# LedController3.net
KiCad netlist of a schematic drawn in EAGLE
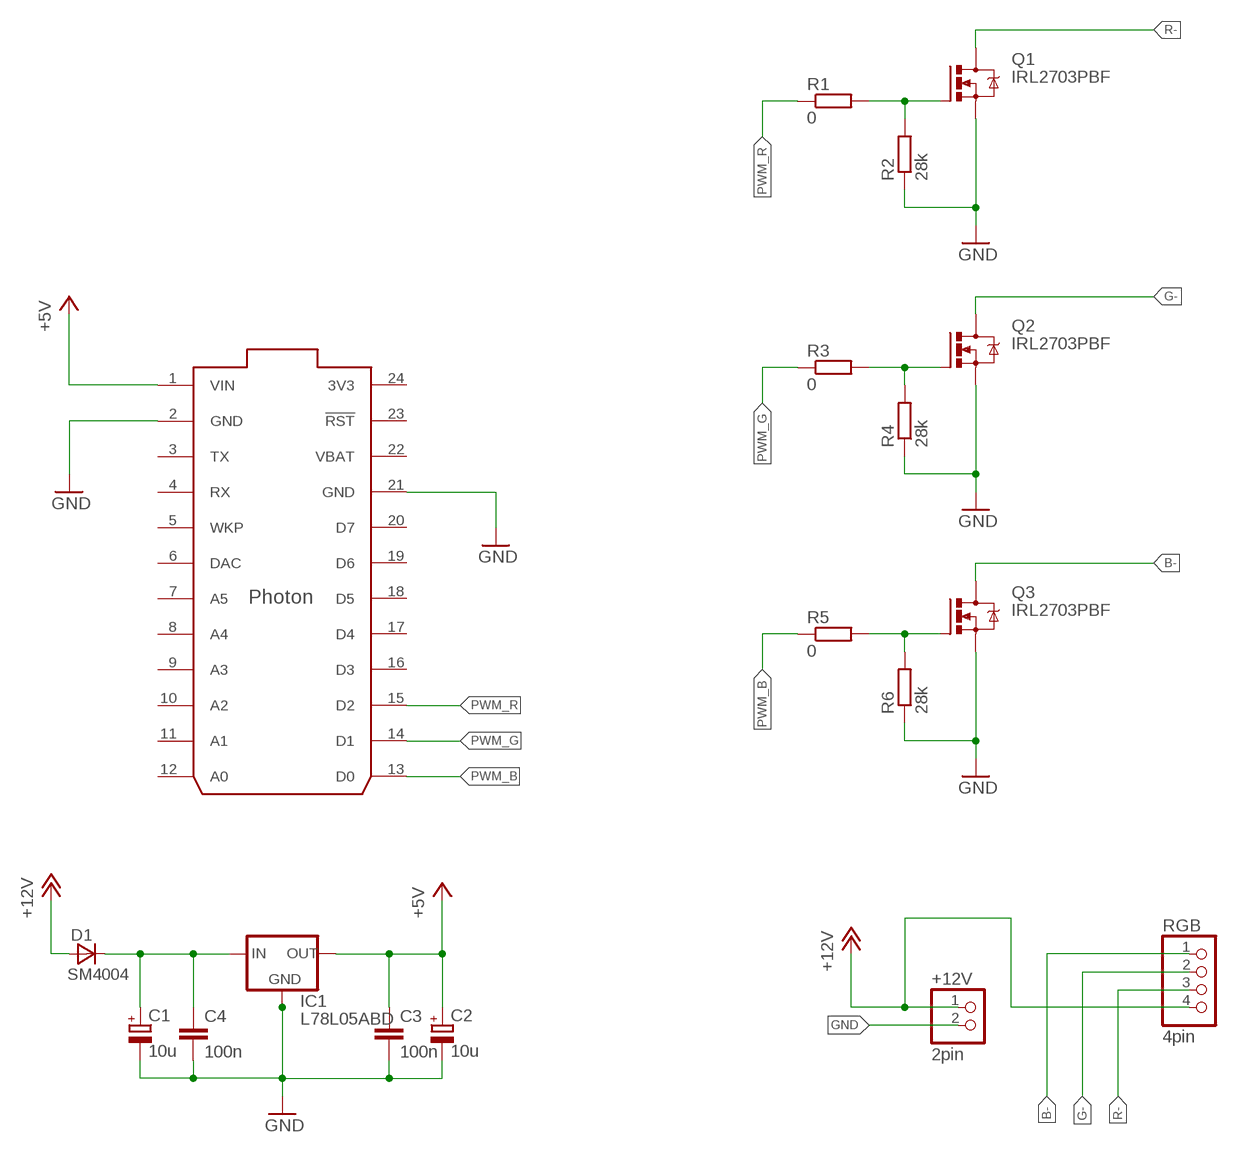
[diagram p0: schematic, sheet 1]

(export (version "E")
  (design (tool "Eeschema 10.0.6"))
  (components
    (comp (ref "+12V")
      (value "2pin")
      (footprint "eagle-import:1X02")
      (libsource (lib "eagle-import") (part "PINHD-1X2"))
    )
    (comp (ref "C1")
      (value "10u")
      (footprint "eagle-import:SMC_C")
      (libsource (lib "eagle-import") (part "CPOL-EUSMCC"))
    )
    (comp (ref "C2")
      (value "10u")
      (footprint "eagle-import:SMC_C")
      (libsource (lib "eagle-import") (part "CPOL-EUSMCC"))
    )
    (comp (ref "C3")
      (value "100n")
      (footprint "eagle-import:C0805")
      (libsource (lib "eagle-import") (part "C-EUC0805"))
    )
    (comp (ref "C4")
      (value "100n")
      (footprint "eagle-import:C0805")
      (libsource (lib "eagle-import") (part "C-EUC0805"))
    )
    (comp (ref "D1")
      (value "SM4004")
      (footprint "eagle-import:MELF-MLL41")
      (libsource (lib "eagle-import") (part "SM4004"))
    )
    (comp (ref "IC1")
      (value "L78L05ABD")
      (footprint "eagle-import:SO08")
      (libsource (lib "eagle-import") (part "L78LXXBD/CD"))
    )
    (comp (ref "Q1")
      (value "IRL2703PBF")
      (footprint "eagle-import:TO220BV")
      (libsource (lib "eagle-import") (part "IRF540"))
    )
    (comp (ref "Q2")
      (value "IRL2703PBF")
      (footprint "eagle-import:TO220BV")
      (libsource (lib "eagle-import") (part "IRF540"))
    )
    (comp (ref "Q3")
      (value "IRL2703PBF")
      (footprint "eagle-import:TO220BV")
      (libsource (lib "eagle-import") (part "IRF540"))
    )
    (comp (ref "R1")
      (value "0")
      (footprint "eagle-import:R0805")
      (libsource (lib "eagle-import") (part "R-EU_R0805"))
    )
    (comp (ref "R2")
      (value "28k")
      (footprint "eagle-import:R0805")
      (libsource (lib "eagle-import") (part "R-EU_R0805"))
    )
    (comp (ref "R3")
      (value "0")
      (footprint "eagle-import:R0805")
      (libsource (lib "eagle-import") (part "R-EU_R0805"))
    )
    (comp (ref "R4")
      (value "28k")
      (footprint "eagle-import:R0805")
      (libsource (lib "eagle-import") (part "R-EU_R0805"))
    )
    (comp (ref "R5")
      (value "0")
      (footprint "eagle-import:R0805")
      (libsource (lib "eagle-import") (part "R-EU_R0805"))
    )
    (comp (ref "R6")
      (value "28k")
      (footprint "eagle-import:R0805")
      (libsource (lib "eagle-import") (part "R-EU_R0805"))
    )
    (comp (ref "RGB")
      (value "4pin")
      (footprint "eagle-import:1X04")
      (libsource (lib "eagle-import") (part "PINHD-1X4"))
    )
    (comp (ref "U$1")
      (value "PHOTON_WITH_HEADERS")
      (footprint "eagle-import:PHOTON")
      (libsource (lib "eagle-import") (part "PHOTON_WITH_HEADERS"))
    )
  )
  (nets
    (net (code "1") (name "+5V") (class "Default")
      (node (ref "C2") (pin "+") (pinfunction "+_+") (pintype "passive"))
      (node (ref "C3") (pin "1") (pinfunction "1_1") (pintype "passive"))
      (node (ref "IC1") (pin "1") (pinfunction "OUT_1") (pintype "passive"))
      (node (ref "U$1") (pin "1") (pinfunction "VIN_1") (pintype "power_in"))
    )
    (net (code "2") (name "+12V") (class "Default")
      (node (ref "+12V") (pin "1") (pinfunction "1_1") (pintype "passive"))
      (node (ref "D1") (pin "A") (pinfunction "A_A") (pintype "passive"))
      (node (ref "RGB") (pin "4") (pinfunction "4_4") (pintype "passive"))
    )
    (net (code "3") (name "/3V3") (class "Default")
      (node (ref "U$1") (pin "24") (pinfunction "3V3_24") (pintype "power_in"))
    )
    (net (code "4") (name "/VBAT") (class "Default")
      (node (ref "U$1") (pin "22") (pinfunction "VBAT_22") (pintype "power_in"))
    )
    (net (code "5") (name "B-") (class "Default")
      (node (ref "Q3") (pin "D") (pinfunction "D_D") (pintype "passive"))
      (node (ref "RGB") (pin "1") (pinfunction "1_1") (pintype "passive"))
    )
    (net (code "6") (name "G-") (class "Default")
      (node (ref "Q2") (pin "D") (pinfunction "D_D") (pintype "passive"))
      (node (ref "RGB") (pin "2") (pinfunction "2_2") (pintype "passive"))
    )
    (net (code "7") (name "GND") (class "Default")
      (node (ref "+12V") (pin "2") (pinfunction "2_2") (pintype "passive"))
      (node (ref "C1") (pin "-") (pinfunction "-_-") (pintype "passive"))
      (node (ref "C2") (pin "-") (pinfunction "-_-") (pintype "passive"))
      (node (ref "C3") (pin "2") (pinfunction "2_2") (pintype "passive"))
      (node (ref "C4") (pin "2") (pinfunction "2_2") (pintype "passive"))
      (node (ref "IC1") (pin "2") (pinfunction "GND1_2") (pintype "input"))
      (node (ref "IC1") (pin "3") (pinfunction "GND2_3") (pintype "input"))
      (node (ref "IC1") (pin "6") (pinfunction "GND3_6") (pintype "input"))
      (node (ref "IC1") (pin "7") (pinfunction "GND4_7") (pintype "input"))
      (node (ref "Q1") (pin "S") (pinfunction "S_S") (pintype "passive"))
      (node (ref "Q2") (pin "S") (pinfunction "S_S") (pintype "passive"))
      (node (ref "Q3") (pin "S") (pinfunction "S_S") (pintype "passive"))
      (node (ref "R2") (pin "1") (pinfunction "1_1") (pintype "passive"))
      (node (ref "R4") (pin "1") (pinfunction "1_1") (pintype "passive"))
      (node (ref "R6") (pin "1") (pinfunction "1_1") (pintype "passive"))
      (node (ref "U$1") (pin "2") (pinfunction "GND_2") (pintype "power_in"))
      (node (ref "U$1") (pin "21") (pinfunction "GND_21") (pintype "power_in"))
    )
    (net (code "8") (name "Net-(IC1-IN)") (class "Default")
      (node (ref "C1") (pin "+") (pinfunction "+_+") (pintype "passive"))
      (node (ref "C4") (pin "1") (pinfunction "1_1") (pintype "passive"))
      (node (ref "D1") (pin "C") (pinfunction "C_C") (pintype "passive"))
      (node (ref "IC1") (pin "8") (pinfunction "IN_8") (pintype "input"))
    )
    (net (code "9") (name "Net-(Q1-PadG)") (class "Default")
      (node (ref "Q1") (pin "G") (pinfunction "G_G") (pintype "passive"))
      (node (ref "R1") (pin "2") (pinfunction "2_2") (pintype "passive"))
      (node (ref "R2") (pin "2") (pinfunction "2_2") (pintype "passive"))
    )
    (net (code "10") (name "Net-(Q2-PadG)") (class "Default")
      (node (ref "Q2") (pin "G") (pinfunction "G_G") (pintype "passive"))
      (node (ref "R3") (pin "2") (pinfunction "2_2") (pintype "passive"))
      (node (ref "R4") (pin "2") (pinfunction "2_2") (pintype "passive"))
    )
    (net (code "11") (name "Net-(Q3-PadG)") (class "Default")
      (node (ref "Q3") (pin "G") (pinfunction "G_G") (pintype "passive"))
      (node (ref "R5") (pin "2") (pinfunction "2_2") (pintype "passive"))
      (node (ref "R6") (pin "2") (pinfunction "2_2") (pintype "passive"))
    )
    (net (code "12") (name "PWM_B") (class "Default")
      (node (ref "R5") (pin "1") (pinfunction "1_1") (pintype "passive"))
      (node (ref "U$1") (pin "13") (pinfunction "D0_13") (pintype "bidirectional"))
    )
    (net (code "13") (name "PWM_G") (class "Default")
      (node (ref "R3") (pin "1") (pinfunction "1_1") (pintype "passive"))
      (node (ref "U$1") (pin "14") (pinfunction "D1_14") (pintype "bidirectional"))
    )
    (net (code "14") (name "PWM_R") (class "Default")
      (node (ref "R1") (pin "1") (pinfunction "1_1") (pintype "passive"))
      (node (ref "U$1") (pin "15") (pinfunction "D2_15") (pintype "bidirectional"))
    )
    (net (code "15") (name "R-") (class "Default")
      (node (ref "Q1") (pin "D") (pinfunction "D_D") (pintype "passive"))
      (node (ref "RGB") (pin "3") (pinfunction "3_3") (pintype "passive"))
    )
    (net (code "16") (name "unconnected-(U$1-A0-Pad12)") (class "Default")
      (node (ref "U$1") (pin "12") (pinfunction "A0_12") (pintype "bidirectional"))
    )
    (net (code "17") (name "unconnected-(U$1-A1-Pad11)") (class "Default")
      (node (ref "U$1") (pin "11") (pinfunction "A1_11") (pintype "bidirectional"))
    )
    (net (code "18") (name "unconnected-(U$1-A2-Pad10)") (class "Default")
      (node (ref "U$1") (pin "10") (pinfunction "A2_10") (pintype "bidirectional"))
    )
    (net (code "19") (name "unconnected-(U$1-A3-Pad9)") (class "Default")
      (node (ref "U$1") (pin "9") (pinfunction "A3_9") (pintype "bidirectional"))
    )
    (net (code "20") (name "unconnected-(U$1-A4-Pad8)") (class "Default")
      (node (ref "U$1") (pin "8") (pinfunction "A4_8") (pintype "bidirectional"))
    )
    (net (code "21") (name "unconnected-(U$1-A5-Pad7)") (class "Default")
      (node (ref "U$1") (pin "7") (pinfunction "A5_7") (pintype "bidirectional"))
    )
    (net (code "22") (name "unconnected-(U$1-D3-Pad16)") (class "Default")
      (node (ref "U$1") (pin "16") (pinfunction "D3_16") (pintype "bidirectional"))
    )
    (net (code "23") (name "unconnected-(U$1-D4-Pad17)") (class "Default")
      (node (ref "U$1") (pin "17") (pinfunction "D4_17") (pintype "bidirectional"))
    )
    (net (code "24") (name "unconnected-(U$1-D5-Pad18)") (class "Default")
      (node (ref "U$1") (pin "18") (pinfunction "D5_18") (pintype "bidirectional"))
    )
    (net (code "25") (name "unconnected-(U$1-D6-Pad19)") (class "Default")
      (node (ref "U$1") (pin "19") (pinfunction "D6_19") (pintype "bidirectional"))
    )
    (net (code "26") (name "unconnected-(U$1-D7-Pad20)") (class "Default")
      (node (ref "U$1") (pin "20") (pinfunction "D7_20") (pintype "bidirectional"))
    )
    (net (code "27") (name "unconnected-(U$1-DAC-Pad6)") (class "Default")
      (node (ref "U$1") (pin "6") (pinfunction "DAC_6") (pintype "bidirectional"))
    )
    (net (code "28") (name "unconnected-(U$1-RX-Pad4)") (class "Default")
      (node (ref "U$1") (pin "4") (pinfunction "RX_4") (pintype "bidirectional"))
    )
    (net (code "29") (name "unconnected-(U$1-TX-Pad3)") (class "Default")
      (node (ref "U$1") (pin "3") (pinfunction "TX_3") (pintype "bidirectional"))
    )
    (net (code "30") (name "unconnected-(U$1-WKP-Pad5)") (class "Default")
      (node (ref "U$1") (pin "5") (pinfunction "WKP_5") (pintype "bidirectional"))
    )
    (net (code "31") (name "unconnected-(U$1-~{RST}-Pad23)") (class "Default")
      (node (ref "U$1") (pin "23") (pinfunction "~{RST}_23") (pintype "bidirectional"))
    )
  )
)
